# Circuits.net
KiCad netlist of a schematic drawn in EAGLE
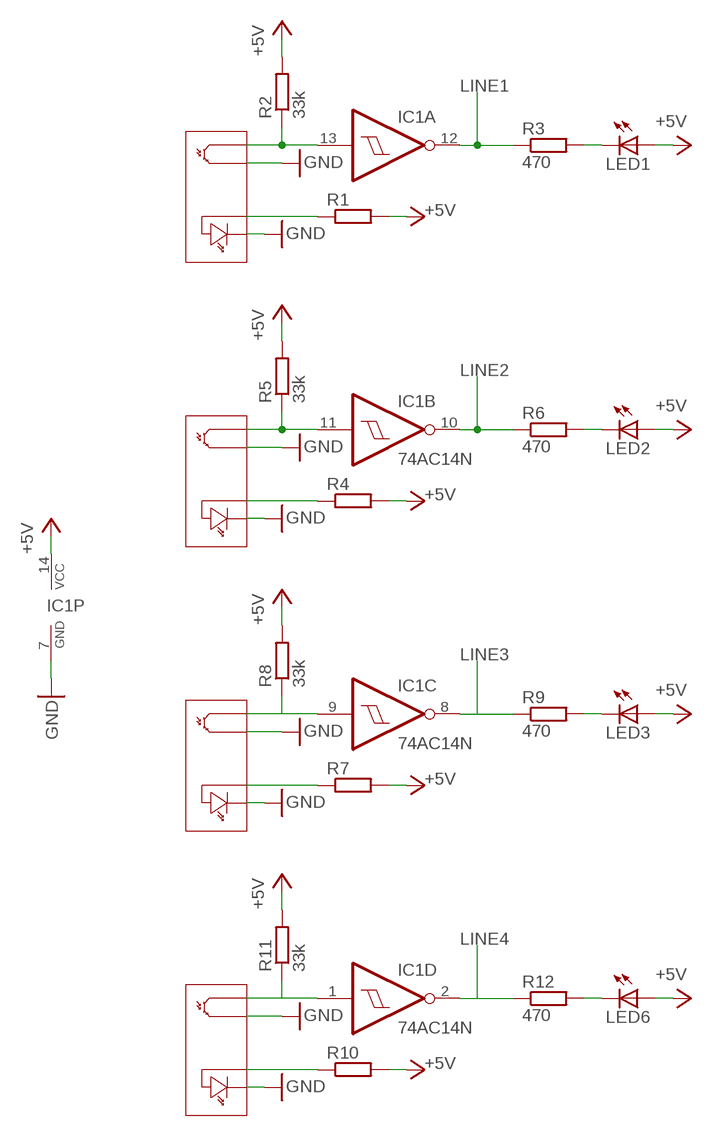
[diagram p0: schematic, sheet 1]
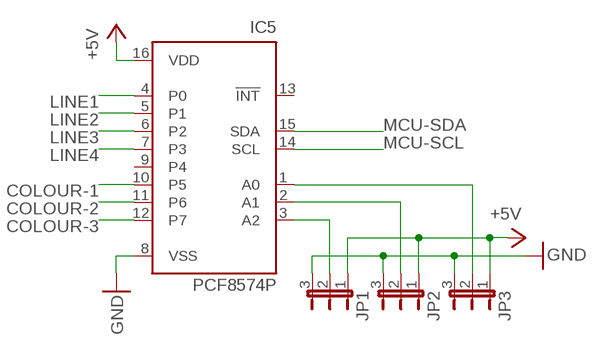
[diagram p1: schematic, sheet 2]
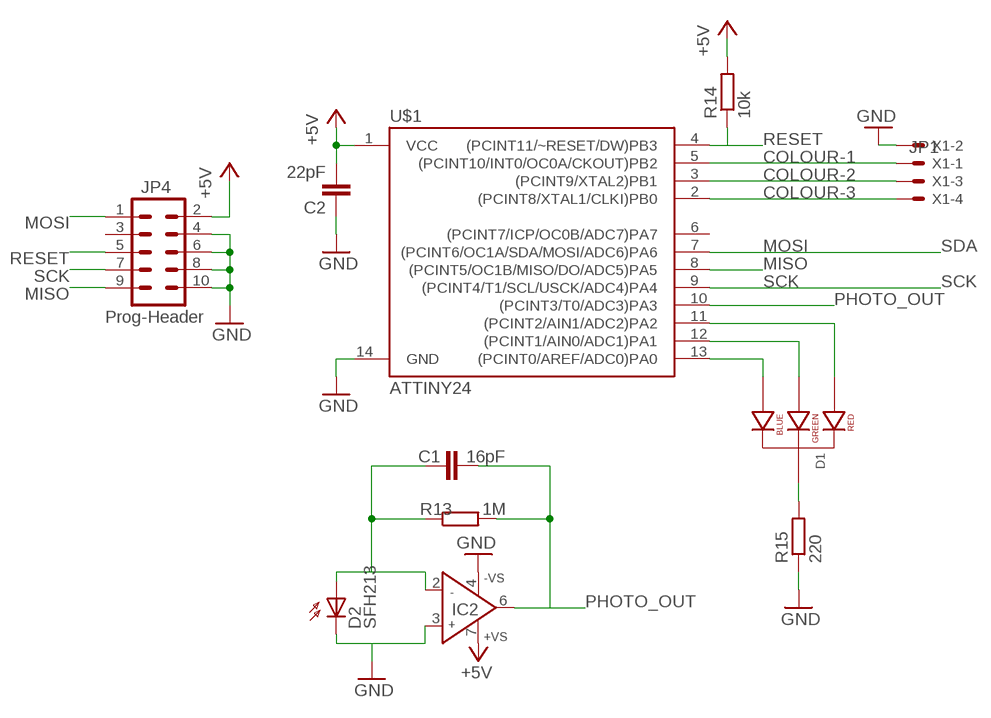
[diagram p2: schematic, sheet 3]
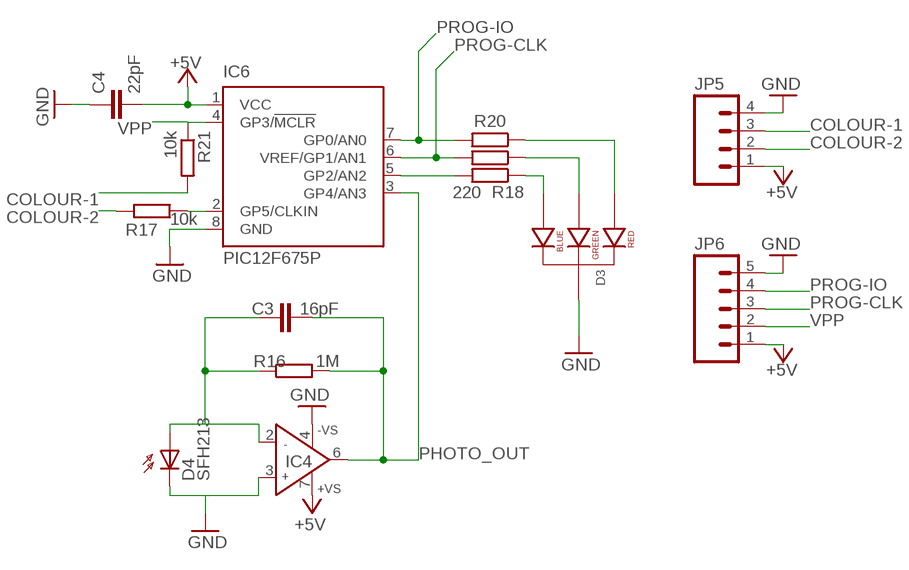
[diagram p3: schematic, sheet 4]

(export (version "E")
  (design (tool "Eeschema 10.0.6"))
  (components
    (comp (ref "C1")
      (value "16pF")
      (footprint "eagle-import:C025-024X044")
      (libsource (lib "eagle-import") (part "C-EU025-024X044"))
    )
    (comp (ref "C2")
      (value "22pF")
      (footprint "eagle-import:C025-024X044")
      (libsource (lib "eagle-import") (part "C-EU025-024X044"))
    )
    (comp (ref "D1")
      (value "LED-RGB-CC-THRUCLEAR")
      (footprint "eagle-import:LED-RGB-THRU")
      (libsource (lib "eagle-import") (part "LED-RGB-CC-THRUCLEAR"))
    )
    (comp (ref "D2")
      (value "SFH213")
      (footprint "eagle-import:SFH205")
      (libsource (lib "eagle-import") (part "SFH205"))
    )
    (comp (ref "IC2")
      (value "mcp603")
      (footprint "eagle-import:DIL08")
      (fields (field (name "MF") "ALTERA CORPORATION") (field (name "MPN") "AD811AN"))
      (libsource (lib "eagle-import") (part "AD811N"))
    )
    (comp (ref "JP4")
      (value "Prog-Header")
      (footprint "eagle-import:2X5-SHROUDED")
      (libsource (lib "eagle-import") (part "M05X2SHD"))
    )
    (comp (ref "R13")
      (value "1M")
      (footprint "eagle-import:0204_5")
      (libsource (lib "eagle-import") (part "R-EU_0204/5"))
    )
    (comp (ref "R14")
      (value "10k")
      (footprint "eagle-import:0207_7")
      (libsource (lib "eagle-import") (part "R-EU_0207/7"))
    )
    (comp (ref "R15")
      (value "220")
      (footprint "eagle-import:0207_7")
      (libsource (lib "eagle-import") (part "R-EU_0207/7"))
    )
    (comp (ref "U$1")
      (value "ATTINY24")
      (footprint "eagle-import:DIL14")
      (libsource (lib "eagle-import") (part "ATTINY84ATTINY84-20PU"))
    )
    (comp (ref "X1")
      (value "JP1")
      (footprint "eagle-import:22-23-2041")
      (fields (field (name "MF") "MOLEX") (field (name "MPN") "22-23-2041"))
      (libsource (lib "eagle-import") (part "22-23-2041"))
    )
    (comp (ref "C3")
      (value "16pF")
      (footprint "eagle-import:C025-024X044")
      (libsource (lib "eagle-import") (part "C-EU025-024X044"))
    )
    (comp (ref "C4")
      (value "22pF")
      (footprint "eagle-import:C025-024X044")
      (libsource (lib "eagle-import") (part "C-EU025-024X044"))
    )
    (comp (ref "D3")
      (value "LED-RGB-CC-THRUCLEAR")
      (footprint "eagle-import:LED-RGB-THRU")
      (libsource (lib "eagle-import") (part "LED-RGB-CC-THRUCLEAR"))
    )
    (comp (ref "D4")
      (value "SFH213")
      (footprint "eagle-import:SFH205")
      (libsource (lib "eagle-import") (part "SFH205"))
    )
    (comp (ref "IC4")
      (value "mcp603")
      (footprint "eagle-import:DIL08")
      (fields (field (name "MF") "ALTERA CORPORATION") (field (name "MPN") "AD811AN"))
      (libsource (lib "eagle-import") (part "AD811N"))
    )
    (comp (ref "IC6")
      (value "PIC12F675P")
      (footprint "eagle-import:DIL8")
      (fields (field (name "MF") "MICROCHIP") (field (name "MPN") "PIC12F675-E/P"))
      (libsource (lib "eagle-import") (part "PIC12F675P"))
    )
    (comp (ref "JP5")
      (value "M04LONGPADS")
      (footprint "eagle-import:1X04_LONGPADS")
      (libsource (lib "eagle-import") (part "M04LONGPADS"))
    )
    (comp (ref "JP6")
      (value "M05PTH_LONGPADS")
      (footprint "eagle-import:1X05_LONGPADS")
      (libsource (lib "eagle-import") (part "M05PTH_LONGPADS"))
    )
    (comp (ref "R16")
      (value "1M")
      (footprint "eagle-import:0204_5")
      (libsource (lib "eagle-import") (part "R-EU_0204/5"))
    )
    (comp (ref "R17")
      (value "10k")
      (footprint "eagle-import:0207_7")
      (libsource (lib "eagle-import") (part "R-EU_0207/7"))
    )
    (comp (ref "R18")
      (value "220")
      (footprint "eagle-import:0207_7")
      (libsource (lib "eagle-import") (part "R-EU_0207/7"))
    )
    (comp (ref "R19")
      (value "220")
      (footprint "eagle-import:0207_7")
      (libsource (lib "eagle-import") (part "R-EU_0207/7"))
    )
    (comp (ref "R20")
      (value "220")
      (footprint "eagle-import:0207_7")
      (libsource (lib "eagle-import") (part "R-EU_0207/7"))
    )
    (comp (ref "R21")
      (value "10k")
      (footprint "eagle-import:0207_7")
      (libsource (lib "eagle-import") (part "R-EU_0207/7"))
    )
    (comp (ref "IC1")
      (value "74AC14N")
      (footprint "eagle-import:DIL14")
      (libsource (lib "eagle-import") (part "7414NAC"))
    )
    (comp (ref "LED1")
      (value "TLLR4400")
      (footprint "eagle-import:LED3MM")
      (fields (field (name "MF") "VISHAY SEMICONDUCTOR"))
      (libsource (lib "eagle-import") (part "TLLR4400"))
    )
    (comp (ref "LED2")
      (value "TLLR4400")
      (footprint "eagle-import:LED3MM")
      (fields (field (name "MF") "VISHAY SEMICONDUCTOR"))
      (libsource (lib "eagle-import") (part "TLLR4400"))
    )
    (comp (ref "LED3")
      (value "TLLR4400")
      (footprint "eagle-import:LED3MM")
      (fields (field (name "MF") "VISHAY SEMICONDUCTOR"))
      (libsource (lib "eagle-import") (part "TLLR4400"))
    )
    (comp (ref "LED6")
      (value "TLLR4400")
      (footprint "eagle-import:LED3MM")
      (fields (field (name "MF") "VISHAY SEMICONDUCTOR"))
      (libsource (lib "eagle-import") (part "TLLR4400"))
    )
    (comp (ref "R1")
      (value "R-EU_0207/7")
      (footprint "eagle-import:0207_7")
      (libsource (lib "eagle-import") (part "R-EU_0207/7"))
    )
    (comp (ref "R2")
      (value "33k")
      (footprint "eagle-import:0207_7")
      (libsource (lib "eagle-import") (part "R-EU_0207/7"))
    )
    (comp (ref "R3")
      (value "470")
      (footprint "eagle-import:0207_7")
      (libsource (lib "eagle-import") (part "R-EU_0207/7"))
    )
    (comp (ref "R4")
      (value "R-EU_0207/7")
      (footprint "eagle-import:0207_7")
      (libsource (lib "eagle-import") (part "R-EU_0207/7"))
    )
    (comp (ref "R5")
      (value "33k")
      (footprint "eagle-import:0207_7")
      (libsource (lib "eagle-import") (part "R-EU_0207/7"))
    )
    (comp (ref "R6")
      (value "470")
      (footprint "eagle-import:0207_7")
      (libsource (lib "eagle-import") (part "R-EU_0207/7"))
    )
    (comp (ref "R7")
      (value "R-EU_0207/7")
      (footprint "eagle-import:0207_7")
      (libsource (lib "eagle-import") (part "R-EU_0207/7"))
    )
    (comp (ref "R8")
      (value "33k")
      (footprint "eagle-import:0207_7")
      (libsource (lib "eagle-import") (part "R-EU_0207/7"))
    )
    (comp (ref "R9")
      (value "470")
      (footprint "eagle-import:0207_7")
      (libsource (lib "eagle-import") (part "R-EU_0207/7"))
    )
    (comp (ref "R10")
      (value "R-EU_0207/7")
      (footprint "eagle-import:0207_7")
      (libsource (lib "eagle-import") (part "R-EU_0207/7"))
    )
    (comp (ref "R11")
      (value "33k")
      (footprint "eagle-import:0207_7")
      (libsource (lib "eagle-import") (part "R-EU_0207/7"))
    )
    (comp (ref "R12")
      (value "470")
      (footprint "eagle-import:0207_7")
      (libsource (lib "eagle-import") (part "R-EU_0207/7"))
    )
    (comp (ref "IC5")
      (value "PCF8574P")
      (footprint "eagle-import:DIL16")
      (fields (field (name "MPN") "PCF8574PN"))
      (libsource (lib "eagle-import") (part "PCF8574P"))
    )
    (comp (ref "JP1")
      (value "JP2W")
      (footprint "eagle-import:JP2W")
      (libsource (lib "eagle-import") (part "JP2W"))
    )
    (comp (ref "JP2")
      (value "JP2W")
      (footprint "eagle-import:JP2W")
      (libsource (lib "eagle-import") (part "JP2W"))
    )
    (comp (ref "JP3")
      (value "JP2W")
      (footprint "eagle-import:JP2W")
      (libsource (lib "eagle-import") (part "JP2W"))
    )
  )
  (nets
    (net (code "1") (name "+5V") (class "Default")
      (node (ref "C2") (pin "2") (pinfunction "2_2") (pintype "passive"))
      (node (ref "C4") (pin "2") (pinfunction "2_2") (pintype "passive"))
      (node (ref "IC1") (pin "14") (pinfunction "VCC_14") (pintype "power_in"))
      (node (ref "IC2") (pin "7") (pinfunction "+VS_7") (pintype "input"))
      (node (ref "IC4") (pin "7") (pinfunction "+VS_7") (pintype "input"))
      (node (ref "IC5") (pin "16") (pinfunction "VDD_16") (pintype "power_in"))
      (node (ref "IC6") (pin "1") (pinfunction "VCC_1") (pintype "power_in"))
      (node (ref "JP1") (pin "1") (pinfunction "1_1") (pintype "passive"))
      (node (ref "JP2") (pin "1") (pinfunction "1_1") (pintype "passive"))
      (node (ref "JP3") (pin "1") (pinfunction "1_1") (pintype "passive"))
      (node (ref "JP4") (pin "2") (pinfunction "2_2") (pintype "passive"))
      (node (ref "JP5") (pin "1") (pinfunction "1_1") (pintype "passive"))
      (node (ref "JP6") (pin "1") (pinfunction "1_1") (pintype "passive"))
      (node (ref "LED1") (pin "A") (pinfunction "A_A") (pintype "passive"))
      (node (ref "LED2") (pin "A") (pinfunction "A_A") (pintype "passive"))
      (node (ref "LED3") (pin "A") (pinfunction "A_A") (pintype "passive"))
      (node (ref "LED6") (pin "A") (pinfunction "A_A") (pintype "passive"))
      (node (ref "R1") (pin "2") (pinfunction "2_2") (pintype "passive"))
      (node (ref "R10") (pin "2") (pinfunction "2_2") (pintype "passive"))
      (node (ref "R11") (pin "2") (pinfunction "2_2") (pintype "passive"))
      (node (ref "R14") (pin "2") (pinfunction "2_2") (pintype "passive"))
      (node (ref "R2") (pin "2") (pinfunction "2_2") (pintype "passive"))
      (node (ref "R4") (pin "2") (pinfunction "2_2") (pintype "passive"))
      (node (ref "R5") (pin "2") (pinfunction "2_2") (pintype "passive"))
      (node (ref "R7") (pin "2") (pinfunction "2_2") (pintype "passive"))
      (node (ref "R8") (pin "2") (pinfunction "2_2") (pintype "passive"))
      (node (ref "U$1") (pin "1") (pinfunction "VCC_1") (pintype "bidirectional"))
    )
    (net (code "2") (name "COLOUR-1") (class "Default")
      (node (ref "IC5") (pin "10") (pinfunction "P5_10") (pintype "bidirectional"))
      (node (ref "JP5") (pin "3") (pinfunction "3_3") (pintype "passive"))
      (node (ref "R21") (pin "2") (pinfunction "2_2") (pintype "passive"))
      (node (ref "U$1") (pin "5") (pinfunction "(PCINT10/INT0/OC0A/CKOUT)PB2_5") (pintype "bidirectional"))
      (node (ref "X1") (pin "1") (pinfunction "S_1") (pintype "passive"))
    )
    (net (code "3") (name "COLOUR-2") (class "Default")
      (node (ref "IC5") (pin "11") (pinfunction "P6_11") (pintype "bidirectional"))
      (node (ref "JP5") (pin "2") (pinfunction "2_2") (pintype "passive"))
      (node (ref "R17") (pin "1") (pinfunction "1_1") (pintype "passive"))
      (node (ref "U$1") (pin "3") (pinfunction "(PCINT9/XTAL2)PB1_3") (pintype "bidirectional"))
      (node (ref "X1") (pin "3") (pinfunction "S_3") (pintype "passive"))
    )
    (net (code "4") (name "COLOUR-3") (class "Default")
      (node (ref "IC5") (pin "12") (pinfunction "P7_12") (pintype "bidirectional"))
      (node (ref "U$1") (pin "2") (pinfunction "(PCINT8/XTAL1/CLKI)PB0_2") (pintype "bidirectional"))
      (node (ref "X1") (pin "4") (pinfunction "S_4") (pintype "passive"))
    )
    (net (code "5") (name "GND") (class "Default")
      (node (ref "C2") (pin "1") (pinfunction "1_1") (pintype "passive"))
      (node (ref "C4") (pin "1") (pinfunction "1_1") (pintype "passive"))
      (node (ref "D2") (pin "K") (pinfunction "C_K") (pintype "passive"))
      (node (ref "D3") (pin "2") (pinfunction "CATHODE_2") (pintype "bidirectional"))
      (node (ref "D4") (pin "K") (pinfunction "C_K") (pintype "passive"))
      (node (ref "IC1") (pin "7") (pinfunction "GND_7") (pintype "power_in"))
      (node (ref "IC2") (pin "3") (pinfunction "IN+_3") (pintype "input"))
      (node (ref "IC2") (pin "4") (pinfunction "-VS_4") (pintype "input"))
      (node (ref "IC4") (pin "3") (pinfunction "IN+_3") (pintype "input"))
      (node (ref "IC4") (pin "4") (pinfunction "-VS_4") (pintype "input"))
      (node (ref "IC5") (pin "8") (pinfunction "VSS_8") (pintype "power_in"))
      (node (ref "IC6") (pin "8") (pinfunction "GND_8") (pintype "power_in"))
      (node (ref "JP1") (pin "3") (pinfunction "3_3") (pintype "passive"))
      (node (ref "JP2") (pin "3") (pinfunction "3_3") (pintype "passive"))
      (node (ref "JP3") (pin "3") (pinfunction "3_3") (pintype "passive"))
      (node (ref "JP4") (pin "10") (pinfunction "10_10") (pintype "passive"))
      (node (ref "JP4") (pin "4") (pinfunction "4_4") (pintype "passive"))
      (node (ref "JP4") (pin "6") (pinfunction "6_6") (pintype "passive"))
      (node (ref "JP4") (pin "8") (pinfunction "8_8") (pintype "passive"))
      (node (ref "JP5") (pin "4") (pinfunction "4_4") (pintype "passive"))
      (node (ref "JP6") (pin "5") (pinfunction "5_5") (pintype "passive"))
      (node (ref "R15") (pin "1") (pinfunction "1_1") (pintype "passive"))
      (node (ref "U$1") (pin "14") (pinfunction "GND_14") (pintype "bidirectional"))
      (node (ref "X1") (pin "2") (pinfunction "S_2") (pintype "passive"))
    )
    (net (code "6") (name "LINE1") (class "Default")
      (node (ref "IC1") (pin "12") (pinfunction "O_12") (pintype "output"))
      (node (ref "IC5") (pin "4") (pinfunction "P0_4") (pintype "bidirectional"))
      (node (ref "R3") (pin "1") (pinfunction "1_1") (pintype "passive"))
    )
    (net (code "7") (name "LINE2") (class "Default")
      (node (ref "IC1") (pin "10") (pinfunction "O_10") (pintype "output"))
      (node (ref "IC5") (pin "5") (pinfunction "P1_5") (pintype "bidirectional"))
      (node (ref "R6") (pin "1") (pinfunction "1_1") (pintype "passive"))
    )
    (net (code "8") (name "LINE3") (class "Default")
      (node (ref "IC1") (pin "8") (pinfunction "O_8") (pintype "output"))
      (node (ref "IC5") (pin "6") (pinfunction "P2_6") (pintype "bidirectional"))
      (node (ref "R9") (pin "1") (pinfunction "1_1") (pintype "passive"))
    )
    (net (code "9") (name "LINE4") (class "Default")
      (node (ref "IC1") (pin "2") (pinfunction "O_2") (pintype "output"))
      (node (ref "IC5") (pin "7") (pinfunction "P3_7") (pintype "bidirectional"))
      (node (ref "R12") (pin "1") (pinfunction "1_1") (pintype "passive"))
    )
    (net (code "10") (name "MCU-SCL") (class "Default")
      (node (ref "IC5") (pin "14") (pinfunction "SCL_14") (pintype "input"))
    )
    (net (code "11") (name "MCU-SDA") (class "Default")
      (node (ref "IC5") (pin "15") (pinfunction "SDA_15") (pintype "bidirectional"))
    )
    (net (code "12") (name "MISO") (class "Default")
      (node (ref "JP4") (pin "9") (pinfunction "9_9") (pintype "passive"))
      (node (ref "U$1") (pin "8") (pinfunction "(PCINT5/OC1B/MISO/DO/ADC5)PA5_8") (pintype "bidirectional"))
    )
    (net (code "13") (name "MOSI") (class "Default")
      (node (ref "JP4") (pin "1") (pinfunction "1_1") (pintype "passive"))
      (node (ref "U$1") (pin "7") (pinfunction "(PCINT6/OC1A/SDA/MOSI/ADC6)PA6_7") (pintype "bidirectional"))
    )
    (net (code "14") (name "Net-(D1-BLUE_CATHODE)") (class "Default")
      (node (ref "D1") (pin "4") (pinfunction "BLUE_CATHODE_4") (pintype "bidirectional"))
      (node (ref "U$1") (pin "13") (pinfunction "(PCINT0/AREF/ADC0)PA0_13") (pintype "bidirectional"))
    )
    (net (code "15") (name "Net-(D1-CATHODE)") (class "Default")
      (node (ref "D1") (pin "2") (pinfunction "CATHODE_2") (pintype "bidirectional"))
      (node (ref "R15") (pin "2") (pinfunction "2_2") (pintype "passive"))
    )
    (net (code "16") (name "Net-(D1-GREEN_CATHODE)") (class "Default")
      (node (ref "D1") (pin "3") (pinfunction "GREEN_CATHODE_3") (pintype "bidirectional"))
      (node (ref "U$1") (pin "12") (pinfunction "(PCINT1/AIN0/ADC1)PA1_12") (pintype "bidirectional"))
    )
    (net (code "17") (name "Net-(D1-RED_CATHODE)") (class "Default")
      (node (ref "D1") (pin "1") (pinfunction "RED_CATHODE_1") (pintype "bidirectional"))
      (node (ref "U$1") (pin "11") (pinfunction "(PCINT2/AIN1/ADC2)PA2_11") (pintype "bidirectional"))
    )
    (net (code "18") (name "Net-(D3-BLUE_CATHODE)") (class "Default")
      (node (ref "D3") (pin "4") (pinfunction "BLUE_CATHODE_4") (pintype "bidirectional"))
      (node (ref "R18") (pin "1") (pinfunction "1_1") (pintype "passive"))
    )
    (net (code "19") (name "Net-(D3-GREEN_CATHODE)") (class "Default")
      (node (ref "D3") (pin "3") (pinfunction "GREEN_CATHODE_3") (pintype "bidirectional"))
      (node (ref "R19") (pin "1") (pinfunction "1_1") (pintype "passive"))
    )
    (net (code "20") (name "Net-(D3-RED_CATHODE)") (class "Default")
      (node (ref "D3") (pin "1") (pinfunction "RED_CATHODE_1") (pintype "bidirectional"))
      (node (ref "R20") (pin "1") (pinfunction "1_1") (pintype "passive"))
    )
    (net (code "21") (name "Net-(IC1A-I)") (class "Default")
      (node (ref "IC1") (pin "13") (pinfunction "I_13") (pintype "input"))
      (node (ref "R2") (pin "1") (pinfunction "1_1") (pintype "passive"))
    )
    (net (code "22") (name "Net-(IC1B-I)") (class "Default")
      (node (ref "IC1") (pin "11") (pinfunction "I_11") (pintype "input"))
      (node (ref "R5") (pin "1") (pinfunction "1_1") (pintype "passive"))
    )
    (net (code "23") (name "Net-(IC1C-I)") (class "Default")
      (node (ref "IC1") (pin "9") (pinfunction "I_9") (pintype "input"))
      (node (ref "R8") (pin "1") (pinfunction "1_1") (pintype "passive"))
    )
    (net (code "24") (name "Net-(IC1D-I)") (class "Default")
      (node (ref "IC1") (pin "1") (pinfunction "I_1") (pintype "input"))
      (node (ref "R11") (pin "1") (pinfunction "1_1") (pintype "passive"))
    )
    (net (code "25") (name "Net-(IC2-IN-)") (class "Default")
      (node (ref "C1") (pin "1") (pinfunction "1_1") (pintype "passive"))
      (node (ref "D2") (pin "A") (pinfunction "A_A") (pintype "passive"))
      (node (ref "IC2") (pin "2") (pinfunction "IN-_2") (pintype "input"))
      (node (ref "R13") (pin "1") (pinfunction "1_1") (pintype "passive"))
    )
    (net (code "26") (name "Net-(IC4-IN-)") (class "Default")
      (node (ref "C3") (pin "1") (pinfunction "1_1") (pintype "passive"))
      (node (ref "D4") (pin "A") (pinfunction "A_A") (pintype "passive"))
      (node (ref "IC4") (pin "2") (pinfunction "IN-_2") (pintype "input"))
      (node (ref "R16") (pin "1") (pinfunction "1_1") (pintype "passive"))
    )
    (net (code "27") (name "Net-(IC5-A0)") (class "Default")
      (node (ref "IC5") (pin "1") (pinfunction "A0_1") (pintype "input"))
      (node (ref "JP3") (pin "2") (pinfunction "2_2") (pintype "passive"))
    )
    (net (code "28") (name "Net-(IC5-A1)") (class "Default")
      (node (ref "IC5") (pin "2") (pinfunction "A1_2") (pintype "input"))
      (node (ref "JP2") (pin "2") (pinfunction "2_2") (pintype "passive"))
    )
    (net (code "29") (name "Net-(IC5-A2)") (class "Default")
      (node (ref "IC5") (pin "3") (pinfunction "A2_3") (pintype "input"))
      (node (ref "JP1") (pin "2") (pinfunction "2_2") (pintype "passive"))
    )
    (net (code "30") (name "Net-(IC6-GP2{slash}AN2)") (class "Default")
      (node (ref "IC6") (pin "5") (pinfunction "GP2/AN2_5") (pintype "bidirectional"))
      (node (ref "R18") (pin "2") (pinfunction "2_2") (pintype "passive"))
    )
    (net (code "31") (name "Net-(IC6-GP5{slash}CLKIN)") (class "Default")
      (node (ref "IC6") (pin "2") (pinfunction "GP5/CLKIN_2") (pintype "bidirectional"))
      (node (ref "R17") (pin "2") (pinfunction "2_2") (pintype "passive"))
    )
    (net (code "32") (name "Net-(LED1-C)") (class "Default")
      (node (ref "LED1") (pin "K") (pinfunction "C_K") (pintype "passive"))
      (node (ref "R3") (pin "2") (pinfunction "2_2") (pintype "passive"))
    )
    (net (code "33") (name "Net-(LED2-C)") (class "Default")
      (node (ref "LED2") (pin "K") (pinfunction "C_K") (pintype "passive"))
      (node (ref "R6") (pin "2") (pinfunction "2_2") (pintype "passive"))
    )
    (net (code "34") (name "Net-(LED3-C)") (class "Default")
      (node (ref "LED3") (pin "K") (pinfunction "C_K") (pintype "passive"))
      (node (ref "R9") (pin "2") (pinfunction "2_2") (pintype "passive"))
    )
    (net (code "35") (name "Net-(LED6-C)") (class "Default")
      (node (ref "LED6") (pin "K") (pinfunction "C_K") (pintype "passive"))
      (node (ref "R12") (pin "2") (pinfunction "2_2") (pintype "passive"))
    )
    (net (code "36") (name "PHOTO_OUT") (class "Default")
      (node (ref "C1") (pin "2") (pinfunction "2_2") (pintype "passive"))
      (node (ref "C3") (pin "2") (pinfunction "2_2") (pintype "passive"))
      (node (ref "IC2") (pin "6") (pinfunction "OUT_6") (pintype "output"))
      (node (ref "IC4") (pin "6") (pinfunction "OUT_6") (pintype "output"))
      (node (ref "IC6") (pin "3") (pinfunction "GP4/AN3_3") (pintype "bidirectional"))
      (node (ref "R13") (pin "2") (pinfunction "2_2") (pintype "passive"))
      (node (ref "R16") (pin "2") (pinfunction "2_2") (pintype "passive"))
      (node (ref "U$1") (pin "10") (pinfunction "(PCINT3/T0/ADC3)PA3_10") (pintype "bidirectional"))
    )
    (net (code "37") (name "PROG-CLK") (class "Default")
      (node (ref "IC6") (pin "6") (pinfunction "VREF/GP1/AN1_6") (pintype "bidirectional"))
      (node (ref "JP6") (pin "3") (pinfunction "3_3") (pintype "passive"))
      (node (ref "R19") (pin "2") (pinfunction "2_2") (pintype "passive"))
    )
    (net (code "38") (name "PROG-IO") (class "Default")
      (node (ref "IC6") (pin "7") (pinfunction "GP0/AN0_7") (pintype "bidirectional"))
      (node (ref "JP6") (pin "4") (pinfunction "4_4") (pintype "passive"))
      (node (ref "R20") (pin "2") (pinfunction "2_2") (pintype "passive"))
    )
    (net (code "39") (name "RESET") (class "Default")
      (node (ref "JP4") (pin "5") (pinfunction "5_5") (pintype "passive"))
      (node (ref "R14") (pin "1") (pinfunction "1_1") (pintype "passive"))
      (node (ref "U$1") (pin "4") (pinfunction "(PCINT11/~{RESET/DW})PB3_4") (pintype "bidirectional"))
    )
    (net (code "40") (name "SCK") (class "Default")
      (node (ref "JP4") (pin "7") (pinfunction "7_7") (pintype "passive"))
      (node (ref "U$1") (pin "9") (pinfunction "(PCINT4/T1/SCL/USCK/ADC4)PA4_9") (pintype "bidirectional"))
    )
    (net (code "41") (name "VPP") (class "Default")
      (node (ref "IC6") (pin "4") (pinfunction "GP3/~{MCLR}_4") (pintype "input"))
      (node (ref "JP6") (pin "2") (pinfunction "2_2") (pintype "passive"))
      (node (ref "R21") (pin "1") (pinfunction "1_1") (pintype "passive"))
    )
    (net (code "42") (name "unconnected-(IC5-P4-Pad9)") (class "Default")
      (node (ref "IC5") (pin "9") (pinfunction "P4_9") (pintype "bidirectional"))
    )
    (net (code "43") (name "unconnected-(IC5-~{INT}-Pad13)") (class "Default")
      (node (ref "IC5") (pin "13") (pinfunction "~{INT}_13") (pintype "output"))
    )
    (net (code "44") (name "unconnected-(JP4-Pad3)") (class "Default")
      (node (ref "JP4") (pin "3") (pinfunction "3_3") (pintype "passive"))
    )
    (net (code "45") (name "unconnected-(R1-Pad1)") (class "Default")
      (node (ref "R1") (pin "1") (pinfunction "1_1") (pintype "passive"))
    )
    (net (code "46") (name "unconnected-(R4-Pad1)") (class "Default")
      (node (ref "R4") (pin "1") (pinfunction "1_1") (pintype "passive"))
    )
    (net (code "47") (name "unconnected-(R7-Pad1)") (class "Default")
      (node (ref "R7") (pin "1") (pinfunction "1_1") (pintype "passive"))
    )
    (net (code "48") (name "unconnected-(R10-Pad1)") (class "Default")
      (node (ref "R10") (pin "1") (pinfunction "1_1") (pintype "passive"))
    )
    (net (code "49") (name "unconnected-(U$1-(PCINT7{slash}ICP{slash}OC0B{slash}ADC7)PA7-Pad6)") (class "Default")
      (node (ref "U$1") (pin "6") (pinfunction "(PCINT7/ICP/OC0B/ADC7)PA7_6") (pintype "bidirectional"))
    )
  )
)
